# STM32_SWD.net
KiCad netlist of a schematic drawn in Altium Designer
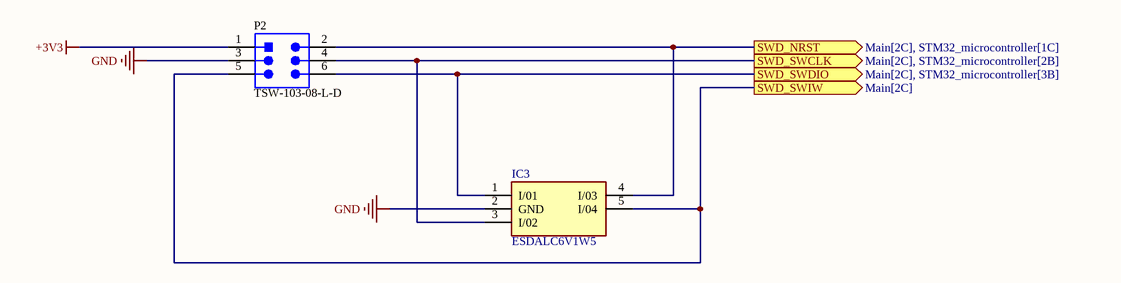
[diagram p0: STM32_SWD.SchDoc]

(export (version "E")
  (design (tool "Eeschema 10.0.6"))
  (components
    (comp (ref "IC3")
      (value "ESDALC6V1W5")
      (footprint "SamacSys:SOT65P210X110-5N")
      (description "Integrated Circuit")
      (fields (field (name "MOUSER PART NUMBER") "511-ESDALC6V1W5"))
      (libsource (lib "*") (part "ESDALC6V1W5"))
    )
    (comp (ref "P2")
      (value "TSW-103-08-L-D")
      (footprint "SMTC-TSW-103-08-L-D_V")
      (fields (field (name "MANUFACTURER") "Samtec"))
      (libsource (lib "Altium Content Vault") (part "CN-2P-M-R6"))
    )
  )
  (nets
    (net (code "1") (name "+3V3") (class "Default")
      (node (ref "P2") (pin "1") (pinfunction "1_1") (pintype "passive"))
    )
    (net (code "2") (name "/SWD_NRST") (class "Default")
      (node (ref "IC3") (pin "4") (pinfunction "I/03_4") (pintype "passive"))
      (node (ref "P2") (pin "2") (pinfunction "2_2") (pintype "passive"))
    )
    (net (code "3") (name "/SWD_SWCLK") (class "Default")
      (node (ref "IC3") (pin "3") (pinfunction "I/02_3") (pintype "passive"))
      (node (ref "P2") (pin "4") (pinfunction "4_4") (pintype "passive"))
    )
    (net (code "4") (name "/SWD_SWDIO") (class "Default")
      (node (ref "IC3") (pin "1") (pinfunction "I/01_1") (pintype "passive"))
      (node (ref "P2") (pin "6") (pinfunction "6_6") (pintype "passive"))
    )
    (net (code "5") (name "/SWD_SWIW") (class "Default")
      (node (ref "IC3") (pin "5") (pinfunction "I/04_5") (pintype "passive"))
      (node (ref "P2") (pin "5") (pinfunction "5_5") (pintype "passive"))
    )
    (net (code "6") (name "GND") (class "Default")
      (node (ref "IC3") (pin "2") (pinfunction "GND_2") (pintype "passive"))
      (node (ref "P2") (pin "3") (pinfunction "3_3") (pintype "passive"))
    )
  )
)
